# current_sensor.net
KiCad netlist of a schematic drawn in Altium Designer
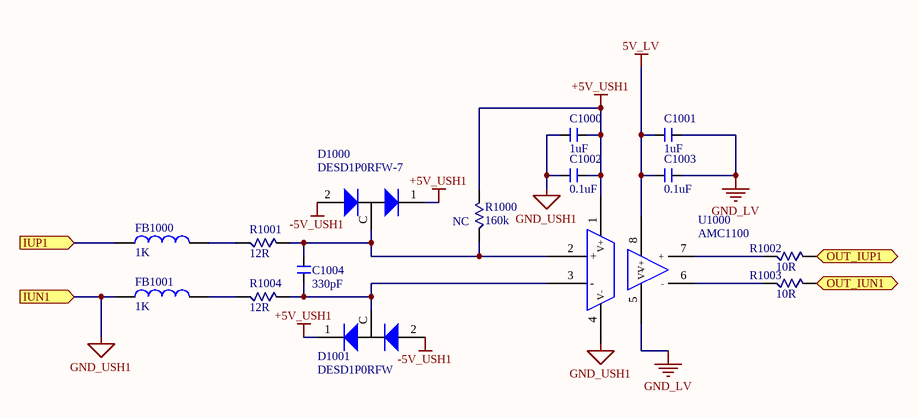
[diagram p0: current sensor.SchDoc]

(export (version "E")
  (design (tool "Eeschema 10.0.6"))
  (components
    (comp (ref "C1000")
      (value "1uF")
      (footprint "0603 (1608 Metric)")
      (description "CAP CER 1UF 50V X5R 0603")
      (fields (field (name "PART") "1276-1860-1-ND") (field (name "Comment") "Cap 0603_new"))
      (libsource (lib "Library_Microgrid") (part "Cap 0603_new"))
    )
    (comp (ref "C1001")
      (value "1uF")
      (footprint "0603 (1608 Metric)")
      (description "CAP CER 1UF 50V X5R 0603")
      (fields (field (name "PART") "1276-1860-1-ND") (field (name "Comment") "Cap 0603_new"))
      (libsource (lib "Library_Microgrid") (part "Cap 0603_new"))
    )
    (comp (ref "C1002")
      (value "0.1uF")
      (footprint "0603 (1608 Metric)")
      (description "CAP CER 0.1UF 50V Y5V 0603")
      (fields (field (name "PART") "311-1343-6-ND") (field (name "Comment") "Cap 0603_new"))
      (libsource (lib "Library_Microgrid") (part "Cap 0603_new"))
    )
    (comp (ref "C1003")
      (value "0.1uF")
      (footprint "0603 (1608 Metric)")
      (description "CAP CER 0.1UF 50V Y5V 0603")
      (fields (field (name "PART") "311-1343-6-ND") (field (name "Comment") "Cap 0603_new"))
      (libsource (lib "Library_Microgrid") (part "Cap 0603_new"))
    )
    (comp (ref "C1004")
      (value "330pF")
      (footprint "0603 (1608 Metric)")
      (description "CAP CER 330PF 50V C0G 0603")
      (fields (field (name "PART") "445-7033-2-ND") (field (name "Comment") "Cap 0603_new"))
      (libsource (lib "Library_Microgrid") (part "Cap 0603_new"))
    )
    (comp (ref "D1000")
      (value "Diode_ESD")
      (footprint "SOT323_ESD")
      (fields (field (name "PART") "DESD1P0RFW-7"))
      (libsource (lib "Library_Microgrid") (part "Diode_ESD"))
    )
    (comp (ref "D1001")
      (value "Diode_ESD")
      (footprint "SOT323_ESD")
      (fields (field (name "PART") "DESD1P0RFW"))
      (libsource (lib "Library_Microgrid") (part "Diode_ESD"))
    )
    (comp (ref "FB1000")
      (value "1K")
      (footprint "0603 (1608 Metric)")
      (description "FERRITE BEAD 1 KOHM 0603 1LN")
      (fields (field (name "PART") "445-8672-1-ND") (field (name "Comment") "Ferrite bead"))
      (libsource (lib "Library_Microgrid") (part "Ferrite bead"))
    )
    (comp (ref "FB1001")
      (value "1K")
      (footprint "0603 (1608 Metric)")
      (description "FERRITE BEAD 1 KOHM 0603 1LN")
      (fields (field (name "PART") "445-8672-1-ND") (field (name "Comment") "Ferrite bead"))
      (libsource (lib "Library_Microgrid") (part "Ferrite bead"))
    )
    (comp (ref "R1000")
      (value "NC")
      (footprint "0603 (1608 Metric)")
      (description "Resistor 0603")
      (fields (field (name "ALTIUM_VALUE") "160k"))
      (libsource (lib "Library_Microgrid") (part "Resistor 0603"))
    )
    (comp (ref "R1001")
      (value "12R")
      (footprint "1206")
      (description "12 Ohm ±0.5% 0.25W, 1/4W Chip Resistor 1206")
      (fields (field (name "PART") "311-2961-1-ND") (field (name "Comment") "Resistor 1206"))
      (libsource (lib "Library_Microgrid") (part "Resistor 1206"))
    )
    (comp (ref "R1002")
      (value "10R")
      (footprint "0603 (1608 Metric)")
      (description "RES SMD 10 OHM 0.05% 1/10W 0603")
      (fields (field (name "PART") "RNCF0603AKT10R0CT-ND") (field (name "Comment") "Resistor 0603"))
      (libsource (lib "Library_Microgrid") (part "Resistor 0603"))
    )
    (comp (ref "R1003")
      (value "10R")
      (footprint "0603 (1608 Metric)")
      (description "RES SMD 10 OHM 0.05% 1/10W 0603")
      (fields (field (name "PART") "RNCF0603AKT10R0CT-ND") (field (name "Comment") "Resistor 0603"))
      (libsource (lib "Library_Microgrid") (part "Resistor 0603"))
    )
    (comp (ref "R1004")
      (value "12R")
      (footprint "1206")
      (description "12 Ohm ±0.5% 0.25W, 1/4W Chip Resistor 1206")
      (fields (field (name "PART") "311-2961-1-ND") (field (name "Comment") "Resistor 1206"))
      (libsource (lib "Library_Microgrid") (part "Resistor 1206"))
    )
    (comp (ref "U1000")
      (value "AMC1100")
      (footprint "SOP8")
      (libsource (lib "Library_Microgrid") (part "AMC1100"))
    )
  )
  (nets
    (net (code "1") (name "+5V_USH1") (class "Default")
      (node (ref "C1000") (pin "2") (pinfunction "OUT_2") (pintype "passive"))
      (node (ref "C1002") (pin "2") (pinfunction "OUT_2") (pintype "passive"))
      (node (ref "D1000") (pin "1") (pinfunction "Anode_1") (pintype "passive"))
      (node (ref "D1001") (pin "1") (pinfunction "Anode_1") (pintype "passive"))
      (node (ref "R1000") (pin "2") (pinfunction "A_2") (pintype "passive"))
      (node (ref "U1000") (pin "1") (pinfunction "V+_1") (pintype "passive"))
    )
    (net (code "2") (name "-5V_USH1") (class "Default")
      (node (ref "D1000") (pin "2") (pinfunction "Anode_2") (pintype "passive"))
      (node (ref "D1001") (pin "2") (pinfunction "Anode_2") (pintype "passive"))
    )
    (net (code "3") (name "/IUP1") (class "Default")
      (node (ref "FB1000") (pin "1") (pinfunction "OUT_1") (pintype "passive"))
    )
    (net (code "4") (name "/OUT_IUN1") (class "Default")
      (node (ref "R1003") (pin "2") (pinfunction "A_2") (pintype "passive"))
    )
    (net (code "5") (name "/OUT_IUP1") (class "Default")
      (node (ref "R1002") (pin "2") (pinfunction "A_2") (pintype "passive"))
    )
    (net (code "6") (name "5V_LV") (class "Default")
      (node (ref "C1001") (pin "1") (pinfunction "OUT_1") (pintype "passive"))
      (node (ref "C1003") (pin "1") (pinfunction "OUT_1") (pintype "passive"))
      (node (ref "U1000") (pin "8") (pinfunction "V+_8") (pintype "passive"))
    )
    (net (code "7") (name "GND_LV") (class "Default")
      (node (ref "C1001") (pin "2") (pinfunction "OUT_2") (pintype "passive"))
      (node (ref "C1003") (pin "2") (pinfunction "OUT_2") (pintype "passive"))
      (node (ref "U1000") (pin "5") (pinfunction "V-_5") (pintype "passive"))
    )
    (net (code "8") (name "GND_USH1") (class "Default")
      (node (ref "C1000") (pin "1") (pinfunction "OUT_1") (pintype "passive"))
      (node (ref "C1002") (pin "1") (pinfunction "OUT_1") (pintype "passive"))
      (node (ref "FB1001") (pin "1") (pinfunction "OUT_1") (pintype "passive"))
      (node (ref "U1000") (pin "4") (pinfunction "V-_4") (pintype "passive"))
    )
    (net (code "9") (name "Net-(D1000-Cathode)") (class "Default")
      (node (ref "C1004") (pin "1") (pinfunction "OUT_1") (pintype "passive"))
      (node (ref "D1000") (pin "C") (pinfunction "Cathode_C") (pintype "passive"))
      (node (ref "R1000") (pin "1") (pinfunction "A_1") (pintype "passive"))
      (node (ref "R1001") (pin "2") (pinfunction "A_2") (pintype "passive"))
      (node (ref "U1000") (pin "2") (pinfunction "+_2") (pintype "passive"))
    )
    (net (code "10") (name "Net-(D1001-Cathode)") (class "Default")
      (node (ref "C1004") (pin "2") (pinfunction "OUT_2") (pintype "passive"))
      (node (ref "D1001") (pin "C") (pinfunction "Cathode_C") (pintype "passive"))
      (node (ref "R1004") (pin "2") (pinfunction "A_2") (pintype "passive"))
      (node (ref "U1000") (pin "3") (pinfunction "-_3") (pintype "passive"))
    )
    (net (code "11") (name "Net-(FB1000-OUT-Pad2)") (class "Default")
      (node (ref "FB1000") (pin "2") (pinfunction "OUT_2") (pintype "passive"))
      (node (ref "R1001") (pin "1") (pinfunction "A_1") (pintype "passive"))
    )
    (net (code "12") (name "Net-(FB1001-OUT-Pad2)") (class "Default")
      (node (ref "FB1001") (pin "2") (pinfunction "OUT_2") (pintype "passive"))
      (node (ref "R1004") (pin "1") (pinfunction "A_1") (pintype "passive"))
    )
    (net (code "13") (name "Net-(R1002-A-Pad1)") (class "Default")
      (node (ref "R1002") (pin "1") (pinfunction "A_1") (pintype "passive"))
      (node (ref "U1000") (pin "7") (pinfunction "+_7") (pintype "passive"))
    )
    (net (code "14") (name "Net-(R1003-A-Pad1)") (class "Default")
      (node (ref "R1003") (pin "1") (pinfunction "A_1") (pintype "passive"))
      (node (ref "U1000") (pin "6") (pinfunction "-_6") (pintype "passive"))
    )
  )
)
